# Buck_regulator.net
KiCad netlist of a schematic drawn in Altium Designer
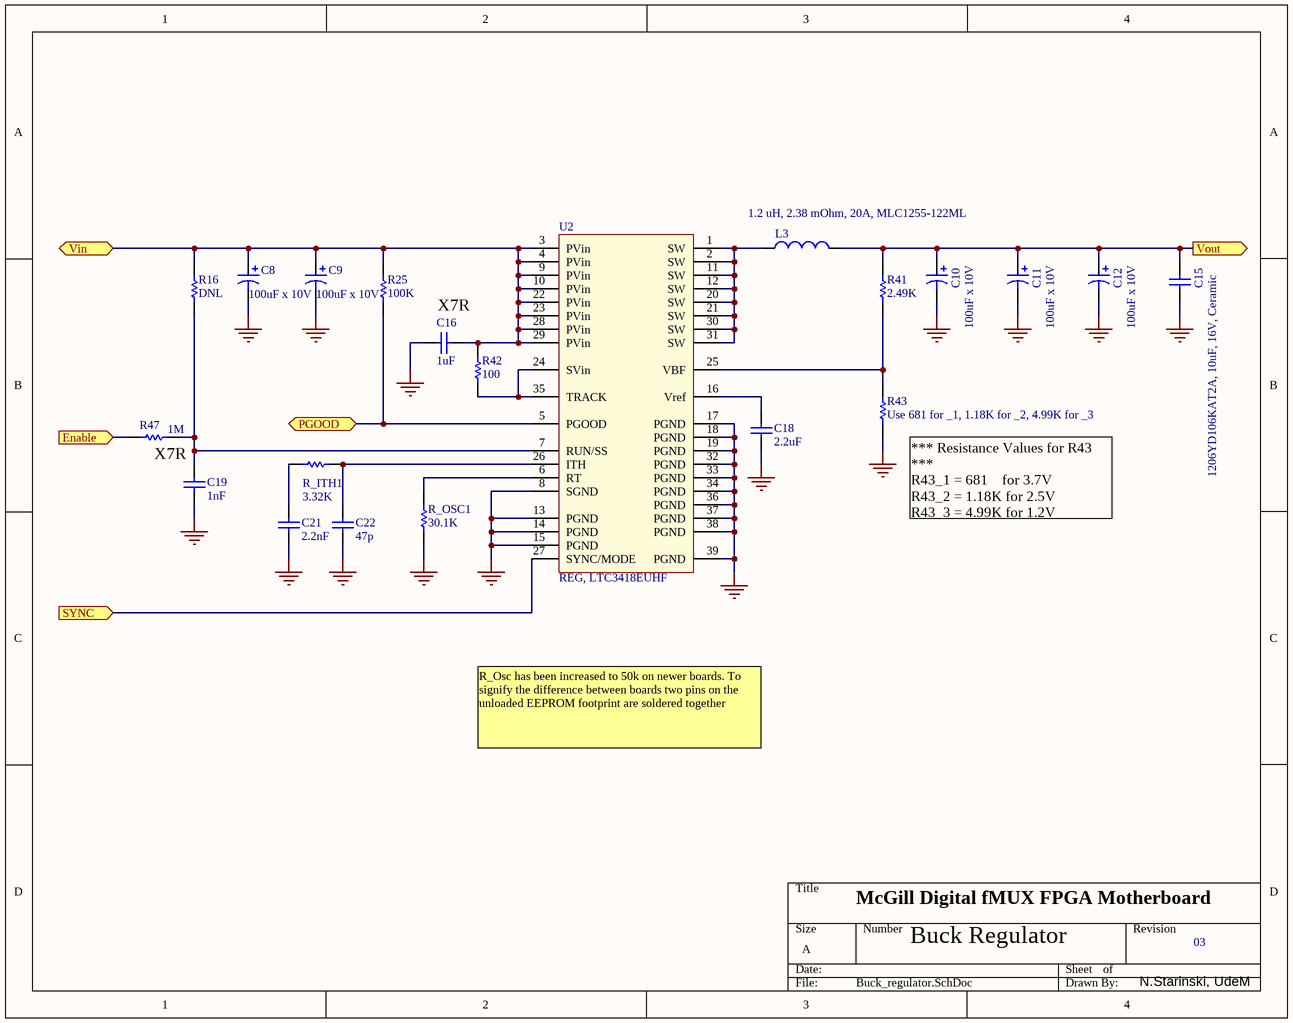
[diagram p0: Buck_regulator.SchDoc]

(export (version "E")
  (design (tool "Eeschema 10.0.6"))
  (components
    (comp (ref "C8")
      (value "100uF x 10V")
      (footprint "TC6032-2412")
      (description "CAP TANTC TPSC107K010R0075")
      (fields (field (name "PUBLISHER") "Altium Limited"))
      (libsource (lib "Miscellaneous Devices 02") (part "Cap Pol3"))
    )
    (comp (ref "C9")
      (value "100uF x 10V")
      (footprint "TC6032-2412")
      (description "CAP TANTC TPSC107K010R0075")
      (fields (field (name "PUBLISHER") "Altium Limited"))
      (libsource (lib "Miscellaneous Devices 02") (part "Cap Pol3"))
    )
    (comp (ref "C10")
      (value "100uF x 10V")
      (footprint "TC6032-2412")
      (description "CAP TANTC TPSC107K010R0075")
      (fields (field (name "PUBLISHER") "Altium Limited"))
      (libsource (lib "Miscellaneous Devices 02") (part "Cap Pol3"))
    )
    (comp (ref "C11")
      (value "100uF x 10V")
      (footprint "TC6032-2412")
      (description "CAP TANTC TPSC107K010R0075")
      (fields (field (name "PUBLISHER") "Altium Limited"))
      (libsource (lib "Miscellaneous Devices 02") (part "Cap Pol3"))
    )
    (comp (ref "C12")
      (value "100uF x 10V")
      (footprint "TC6032-2412")
      (description "CAP TANTC TPSC107K010R0075")
      (fields (field (name "PUBLISHER") "Altium Limited"))
      (libsource (lib "Miscellaneous Devices 02") (part "Cap Pol3"))
    )
    (comp (ref "C15")
      (value "1206YD106KAT2A, 10uF, 16V, Ceramic")
      (footprint "CC3225-1210")
      (description "CAP POL 1206YD106KAT2A")
      (fields (field (name "PUBLISHER") "Altium Limited"))
      (libsource (lib "Miscellaneous Devices") (part "Cap Semi"))
    )
    (comp (ref "C16")
      (value "1uF")
      (footprint "CC1608-0603")
      (description "Capacitor (Semiconductor SIM Model)")
      (fields (field (name "PUBLISHER") "Altium Limited"))
      (libsource (lib "Miscellaneous Devices") (part "Cap Semi"))
    )
    (comp (ref "C18")
      (value "2.2uF")
      (footprint "CC3225-1210")
      (description "Capacitor (use 1206 footprint)")
      (fields (field (name "PUBLISHER") "Altium Limited"))
      (libsource (lib "Miscellaneous Devices") (part "Cap Semi"))
    )
    (comp (ref "C19")
      (value "1nF")
      (footprint "CC1608-0603")
      (description "Capacitor (Semiconductor SIM Model)")
      (fields (field (name "PUBLISHER") "Altium Limited"))
      (libsource (lib "Miscellaneous Devices") (part "Cap Semi"))
    )
    (comp (ref "C21")
      (value "2.2nF")
      (footprint "CC1608-0603")
      (description "Capacitor (Semiconductor SIM Model)")
      (fields (field (name "PUBLISHER") "Altium Limited"))
      (libsource (lib "Miscellaneous Devices") (part "Cap Semi"))
    )
    (comp (ref "C22")
      (value "47p")
      (footprint "CC1608-0603")
      (description "Capacitor (Semiconductor SIM Model)")
      (fields (field (name "PUBLISHER") "Altium Limited"))
      (libsource (lib "Miscellaneous Devices") (part "Cap Semi"))
    )
    (comp (ref "L3")
      (value "1.2 uH, 2.38 mOhm, 20A, MLC1255-122ML")
      (footprint "MLC_inductor")
      (description "Inductor")
      (fields (field (name "PUBLISHER") "Altium Limited"))
      (libsource (lib "Miscellaneous Devices") (part "Inductor"))
    )
    (comp (ref "R16")
      (value "DNL")
      (footprint "CR1608-0603")
      (description "Semiconductor Resistor")
      (fields (field (name "PUBLISHER") "Altium Limited"))
      (libsource (lib "Miscellaneous Devices") (part "Res Semi"))
    )
    (comp (ref "R25")
      (value "100K")
      (footprint "CR1608-0603")
      (description "Semiconductor Resistor")
      (fields (field (name "PUBLISHER") "Altium Limited"))
      (libsource (lib "Miscellaneous Devices") (part "Res Semi"))
    )
    (comp (ref "R41")
      (value "2.49K")
      (footprint "CR1608-0603")
      (description "Resistor 0603")
      (fields (field (name "PUBLISHER") "Altium Limited"))
      (libsource (lib "Miscellaneous Devices") (part "Res Semi"))
    )
    (comp (ref "R42")
      (value "100")
      (footprint "CR1608-0603")
      (description "Semiconductor Resistor")
      (fields (field (name "PUBLISHER") "Altium Limited"))
      (libsource (lib "Miscellaneous Devices") (part "Res Semi"))
    )
    (comp (ref "R43")
      (value "Use 681 for _1, 1.18K for _2, 4.99K for _3")
      (footprint "CR1608-0603")
      (description "Semiconductor Resistor")
      (fields (field (name "PUBLISHER") "Altium Limited"))
      (libsource (lib "Miscellaneous Devices") (part "Res Semi"))
    )
    (comp (ref "R47")
      (value "1M")
      (footprint "CR1608-0603")
      (description "Resistor 0603")
      (fields (field (name "PUBLISHER") "Altium Limited"))
      (libsource (lib "Miscellaneous Devices") (part "Res Semi"))
    )
    (comp (ref "R_ITH1")
      (value "3.32K")
      (footprint "CR1608-0603")
      (description "Resistor 0603")
      (fields (field (name "PUBLISHER") "Altium Limited"))
      (libsource (lib "Miscellaneous Devices") (part "Res Semi"))
    )
    (comp (ref "R_OSC1")
      (value "30.1K")
      (footprint "CR1608-0603")
      (description "Resistor 0603")
      (fields (field (name "PUBLISHER") "Altium Limited"))
      (libsource (lib "Miscellaneous Devices") (part "Res Semi"))
    )
    (comp (ref "U2")
      (value "REG, LTC3418EUHF")
      (footprint "UH38_N")
      (description "8A, 4MHz, Monolithic Syncronous Step-Down Regulator")
      (libsource (lib "LT Power Mgt DC-DC Converter") (part "LTC3418"))
    )
  )
  (nets
    (net (code "1") (name "/Enable") (class "Default")
      (node (ref "R47") (pin "1") (pinfunction "1_1") (pintype "passive"))
    )
    (net (code "2") (name "/PGOOD") (class "Default")
      (node (ref "R25") (pin "1") (pinfunction "1_1") (pintype "passive"))
      (node (ref "U2") (pin "5") (pinfunction "PGOOD_5") (pintype "passive"))
    )
    (net (code "3") (name "/SYNC") (class "Default")
      (node (ref "U2") (pin "27") (pinfunction "SYNC/MODE_27") (pintype "passive"))
    )
    (net (code "4") (name "/Vin") (class "Default")
      (node (ref "C16") (pin "2") (pinfunction "2_2") (pintype "passive"))
      (node (ref "C8") (pin "1") (pinfunction "1_1") (pintype "passive"))
      (node (ref "C9") (pin "1") (pinfunction "1_1") (pintype "passive"))
      (node (ref "R16") (pin "2") (pinfunction "2_2") (pintype "passive"))
      (node (ref "R25") (pin "2") (pinfunction "2_2") (pintype "passive"))
      (node (ref "R42") (pin "2") (pinfunction "2_2") (pintype "passive"))
      (node (ref "U2") (pin "10") (pinfunction "PVin_10") (pintype "power_in"))
      (node (ref "U2") (pin "22") (pinfunction "PVin_22") (pintype "power_in"))
      (node (ref "U2") (pin "23") (pinfunction "PVin_23") (pintype "power_in"))
      (node (ref "U2") (pin "28") (pinfunction "PVin_28") (pintype "power_in"))
      (node (ref "U2") (pin "29") (pinfunction "PVin_29") (pintype "power_in"))
      (node (ref "U2") (pin "3") (pinfunction "PVin_3") (pintype "power_in"))
      (node (ref "U2") (pin "4") (pinfunction "PVin_4") (pintype "power_in"))
      (node (ref "U2") (pin "9") (pinfunction "PVin_9") (pintype "power_in"))
    )
    (net (code "5") (name "/Vout") (class "Default")
      (node (ref "C10") (pin "1") (pinfunction "1_1") (pintype "passive"))
      (node (ref "C11") (pin "1") (pinfunction "1_1") (pintype "passive"))
      (node (ref "C12") (pin "1") (pinfunction "1_1") (pintype "passive"))
      (node (ref "C15") (pin "1") (pinfunction "1_1") (pintype "passive"))
      (node (ref "L3") (pin "2") (pinfunction "2_2") (pintype "passive"))
      (node (ref "R41") (pin "2") (pinfunction "2_2") (pintype "passive"))
    )
    (net (code "6") (name "GND") (class "Default")
      (node (ref "C10") (pin "2") (pinfunction "2_2") (pintype "passive"))
      (node (ref "C11") (pin "2") (pinfunction "2_2") (pintype "passive"))
      (node (ref "C12") (pin "2") (pinfunction "2_2") (pintype "passive"))
      (node (ref "C15") (pin "2") (pinfunction "2_2") (pintype "passive"))
      (node (ref "C16") (pin "1") (pinfunction "1_1") (pintype "passive"))
      (node (ref "C18") (pin "1") (pinfunction "1_1") (pintype "passive"))
      (node (ref "C19") (pin "1") (pinfunction "1_1") (pintype "passive"))
      (node (ref "C21") (pin "1") (pinfunction "1_1") (pintype "passive"))
      (node (ref "C22") (pin "1") (pinfunction "1_1") (pintype "passive"))
      (node (ref "C8") (pin "2") (pinfunction "2_2") (pintype "passive"))
      (node (ref "C9") (pin "2") (pinfunction "2_2") (pintype "passive"))
      (node (ref "R43") (pin "1") (pinfunction "1_1") (pintype "passive"))
      (node (ref "R_OSC1") (pin "1") (pinfunction "1_1") (pintype "passive"))
      (node (ref "U2") (pin "13") (pinfunction "PGND_13") (pintype "power_in"))
      (node (ref "U2") (pin "14") (pinfunction "PGND_14") (pintype "power_in"))
      (node (ref "U2") (pin "15") (pinfunction "PGND_15") (pintype "power_in"))
      (node (ref "U2") (pin "17") (pinfunction "PGND_17") (pintype "power_in"))
      (node (ref "U2") (pin "18") (pinfunction "PGND_18") (pintype "power_in"))
      (node (ref "U2") (pin "19") (pinfunction "PGND_19") (pintype "power_in"))
      (node (ref "U2") (pin "32") (pinfunction "PGND_32") (pintype "power_in"))
      (node (ref "U2") (pin "33") (pinfunction "PGND_33") (pintype "power_in"))
      (node (ref "U2") (pin "34") (pinfunction "PGND_34") (pintype "power_in"))
      (node (ref "U2") (pin "36") (pinfunction "PGND_36") (pintype "power_in"))
      (node (ref "U2") (pin "37") (pinfunction "PGND_37") (pintype "power_in"))
      (node (ref "U2") (pin "38") (pinfunction "PGND_38") (pintype "power_in"))
      (node (ref "U2") (pin "39") (pinfunction "PGND_39") (pintype "power_in"))
      (node (ref "U2") (pin "8") (pinfunction "SGND_8") (pintype "power_in"))
    )
    (net (code "7") (name "Net-(C21-Pad2)") (class "Default")
      (node (ref "C21") (pin "2") (pinfunction "2_2") (pintype "passive"))
      (node (ref "R_ITH1") (pin "1") (pinfunction "1_1") (pintype "passive"))
    )
    (net (code "8") (name "Net-(L3-Pad1)") (class "Default")
      (node (ref "L3") (pin "1") (pinfunction "1_1") (pintype "passive"))
      (node (ref "U2") (pin "1") (pinfunction "SW_1") (pintype "passive"))
      (node (ref "U2") (pin "11") (pinfunction "SW_11") (pintype "passive"))
      (node (ref "U2") (pin "12") (pinfunction "SW_12") (pintype "passive"))
      (node (ref "U2") (pin "2") (pinfunction "SW_2") (pintype "passive"))
      (node (ref "U2") (pin "20") (pinfunction "SW_20") (pintype "passive"))
      (node (ref "U2") (pin "21") (pinfunction "SW_21") (pintype "passive"))
      (node (ref "U2") (pin "30") (pinfunction "SW_30") (pintype "passive"))
      (node (ref "U2") (pin "31") (pinfunction "SW_31") (pintype "passive"))
    )
    (net (code "9") (name "Net-(U2-ITH)") (class "Default")
      (node (ref "C22") (pin "2") (pinfunction "2_2") (pintype "passive"))
      (node (ref "R_ITH1") (pin "2") (pinfunction "2_2") (pintype "passive"))
      (node (ref "U2") (pin "26") (pinfunction "ITH_26") (pintype "passive"))
    )
    (net (code "10") (name "Net-(U2-RT)") (class "Default")
      (node (ref "R_OSC1") (pin "2") (pinfunction "2_2") (pintype "passive"))
      (node (ref "U2") (pin "6") (pinfunction "RT_6") (pintype "passive"))
    )
    (net (code "11") (name "Net-(U2-RUN{slash}SS)") (class "Default")
      (node (ref "C19") (pin "2") (pinfunction "2_2") (pintype "passive"))
      (node (ref "R16") (pin "1") (pinfunction "1_1") (pintype "passive"))
      (node (ref "R47") (pin "2") (pinfunction "2_2") (pintype "passive"))
      (node (ref "U2") (pin "7") (pinfunction "RUN/SS_7") (pintype "passive"))
    )
    (net (code "12") (name "Net-(U2-SVin)") (class "Default")
      (node (ref "R42") (pin "1") (pinfunction "1_1") (pintype "passive"))
      (node (ref "U2") (pin "24") (pinfunction "SVin_24") (pintype "passive"))
      (node (ref "U2") (pin "35") (pinfunction "TRACK_35") (pintype "passive"))
    )
    (net (code "13") (name "Net-(U2-VBF)") (class "Default")
      (node (ref "R41") (pin "1") (pinfunction "1_1") (pintype "passive"))
      (node (ref "R43") (pin "2") (pinfunction "2_2") (pintype "passive"))
      (node (ref "U2") (pin "25") (pinfunction "VBF_25") (pintype "passive"))
    )
    (net (code "14") (name "Net-(U2-Vref)") (class "Default")
      (node (ref "C18") (pin "2") (pinfunction "2_2") (pintype "passive"))
      (node (ref "U2") (pin "16") (pinfunction "Vref_16") (pintype "passive"))
    )
  )
)
